# STM32.net
KiCad netlist of a schematic drawn in Altium Designer
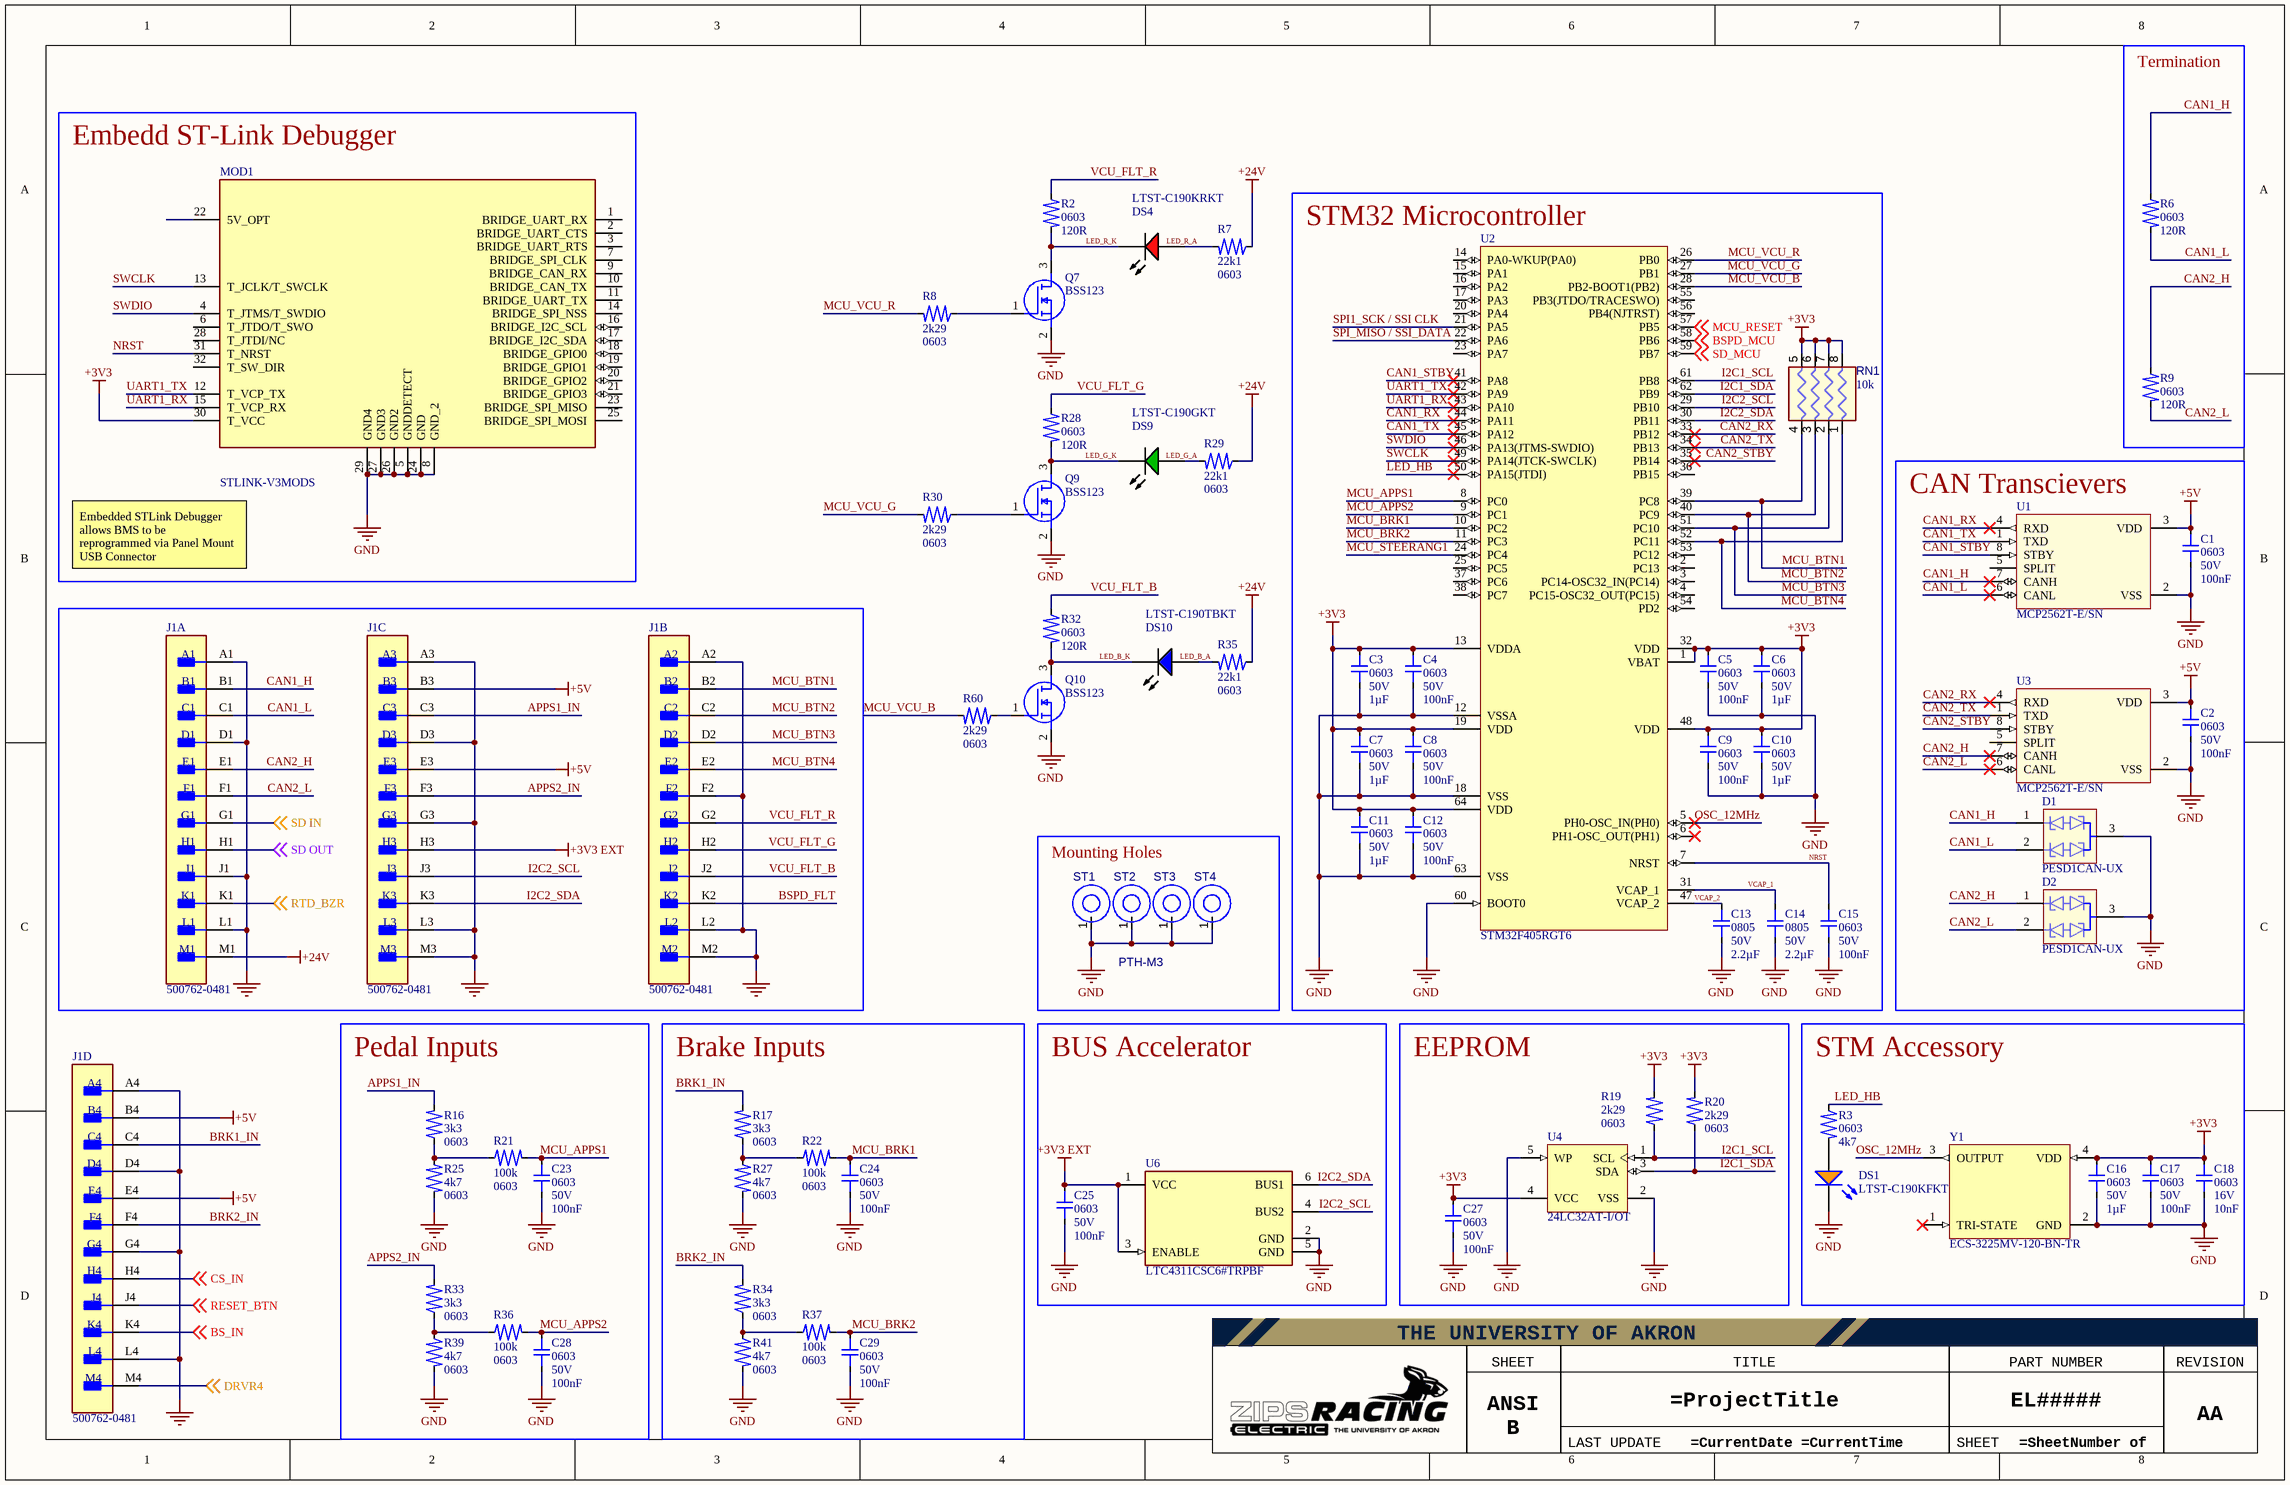
[diagram p0: STM32.SchDoc]

(export (version "E")
  (design (tool "Eeschema 10.0.6"))
  (components
    (comp (ref "C1")
      (value "100nF")
      (footprint "0603")
      (description "Capacitor, 0603, 5%")
      (fields (field (name "VOLTAGE") "50V") (field (name "Comment") "Capacitor 100nF 0603 5%"))
      (libsource (lib "Zips Racing Electric") (part "CAP-0603"))
    )
    (comp (ref "C2")
      (value "100nF")
      (footprint "0603")
      (description "Capacitor, 0603, 5%")
      (fields (field (name "VOLTAGE") "50V") (field (name "Comment") "Capacitor 100nF 0603 5%"))
      (libsource (lib "Zips Racing Electric") (part "CAP-0603"))
    )
    (comp (ref "C3")
      (value "1µF")
      (footprint "0603")
      (description "Capacitor, 0603, 5%")
      (fields (field (name "VOLTAGE") "50V") (field (name "Comment") "Capacitor 1uF 0603 5%"))
      (libsource (lib "Zips Racing Electric") (part "CAP-0603"))
    )
    (comp (ref "C4")
      (value "100nF")
      (footprint "0603")
      (description "Capacitor, 0603, 5%")
      (fields (field (name "VOLTAGE") "50V") (field (name "Comment") "Capacitor 100nF 0603 5%"))
      (libsource (lib "Zips Racing Electric") (part "CAP-0603"))
    )
    (comp (ref "C5")
      (value "100nF")
      (footprint "0603")
      (description "Capacitor, 0603, 5%")
      (fields (field (name "VOLTAGE") "50V") (field (name "Comment") "Capacitor 100nF 0603 5%"))
      (libsource (lib "Zips Racing Electric") (part "CAP-0603"))
    )
    (comp (ref "C6")
      (value "1µF")
      (footprint "0603")
      (description "Capacitor, 0603, 5%")
      (fields (field (name "VOLTAGE") "50V") (field (name "Comment") "Capacitor 1uF 0603 5%"))
      (libsource (lib "Zips Racing Electric") (part "CAP-0603"))
    )
    (comp (ref "C7")
      (value "1µF")
      (footprint "0603")
      (description "Capacitor, 0603, 5%")
      (fields (field (name "VOLTAGE") "50V") (field (name "Comment") "Capacitor 1uF 0603 5%"))
      (libsource (lib "Zips Racing Electric") (part "CAP-0603"))
    )
    (comp (ref "C8")
      (value "100nF")
      (footprint "0603")
      (description "Capacitor, 0603, 5%")
      (fields (field (name "VOLTAGE") "50V") (field (name "Comment") "Capacitor 100nF 0603 5%"))
      (libsource (lib "Zips Racing Electric") (part "CAP-0603"))
    )
    (comp (ref "C9")
      (value "100nF")
      (footprint "0603")
      (description "Capacitor, 0603, 5%")
      (fields (field (name "VOLTAGE") "50V") (field (name "Comment") "Capacitor 100nF 0603 5%"))
      (libsource (lib "Zips Racing Electric") (part "CAP-0603"))
    )
    (comp (ref "C10")
      (value "1µF")
      (footprint "0603")
      (description "Capacitor, 0603, 5%")
      (fields (field (name "VOLTAGE") "50V") (field (name "Comment") "Capacitor 1uF 0603 5%"))
      (libsource (lib "Zips Racing Electric") (part "CAP-0603"))
    )
    (comp (ref "C11")
      (value "1µF")
      (footprint "0603")
      (description "Capacitor, 0603, 5%")
      (fields (field (name "VOLTAGE") "50V") (field (name "Comment") "Capacitor 1uF 0603 5%"))
      (libsource (lib "Zips Racing Electric") (part "CAP-0603"))
    )
    (comp (ref "C12")
      (value "100nF")
      (footprint "0603")
      (description "Capacitor, 0603, 5%")
      (fields (field (name "VOLTAGE") "50V") (field (name "Comment") "Capacitor 100nF 0603 5%"))
      (libsource (lib "Zips Racing Electric") (part "CAP-0603"))
    )
    (comp (ref "C13")
      (value "2.2µF")
      (footprint "0805")
      (description "Capacitor, 0805, 5%")
      (fields (field (name "VOLTAGE") "50V") (field (name "Comment") "Capacitor 2.2F 0805 5%"))
      (libsource (lib "Zips Racing Electric") (part "CAP-0603"))
    )
    (comp (ref "C14")
      (value "2.2µF")
      (footprint "0805")
      (description "Capacitor, 0805, 5%")
      (fields (field (name "VOLTAGE") "50V") (field (name "Comment") "Capacitor 2.2F 0805 5%"))
      (libsource (lib "Zips Racing Electric") (part "CAP-0603"))
    )
    (comp (ref "C15")
      (value "100nF")
      (footprint "0603")
      (description "Capacitor, 0603, 5%")
      (fields (field (name "VOLTAGE") "50V") (field (name "Comment") "Capacitor 100nF 0603 5%"))
      (libsource (lib "Zips Racing Electric") (part "CAP-0603"))
    )
    (comp (ref "C16")
      (value "1µF")
      (footprint "0603")
      (description "Capacitor, 0603, 5%")
      (fields (field (name "VOLTAGE") "50V") (field (name "Comment") "Capacitor 1uF 0603 5%"))
      (libsource (lib "Zips Racing Electric") (part "CAP-0603"))
    )
    (comp (ref "C17")
      (value "100nF")
      (footprint "0603")
      (description "Capacitor, 0603, 5%")
      (fields (field (name "VOLTAGE") "50V") (field (name "Comment") "Capacitor 100nF 0603 5%"))
      (libsource (lib "Zips Racing Electric") (part "CAP-0603"))
    )
    (comp (ref "C18")
      (value "10nF")
      (footprint "0603")
      (description "Capacitor, 0603, 5%")
      (fields (field (name "VOLTAGE") "16V") (field (name "Comment") "Capacitor 10nF 0603 5%"))
      (libsource (lib "Zips Racing Electric") (part "CAP-0603"))
    )
    (comp (ref "C23")
      (value "100nF")
      (footprint "0603")
      (description "Capacitor, 0603, 5%")
      (fields (field (name "VOLTAGE") "50V") (field (name "Comment") "Capacitor 100nF 0603 5%"))
      (libsource (lib "Zips Racing Electric") (part "CAP-0603"))
    )
    (comp (ref "C24")
      (value "100nF")
      (footprint "0603")
      (description "Capacitor, 0603, 5%")
      (fields (field (name "VOLTAGE") "50V") (field (name "Comment") "Capacitor 100nF 0603 5%"))
      (libsource (lib "Zips Racing Electric") (part "CAP-0603"))
    )
    (comp (ref "C25")
      (value "100nF")
      (footprint "0603")
      (description "Capacitor, 0603, 5%")
      (fields (field (name "VOLTAGE") "50V") (field (name "Comment") "Capacitor 100nF 0603 5%"))
      (libsource (lib "Zips Racing Electric") (part "CAP-0603"))
    )
    (comp (ref "C27")
      (value "100nF")
      (footprint "0603")
      (description "Capacitor, 0603, 5%")
      (fields (field (name "VOLTAGE") "50V") (field (name "Comment") "Capacitor 100nF 0603 5%"))
      (libsource (lib "Zips Racing Electric") (part "CAP-0603"))
    )
    (comp (ref "C28")
      (value "100nF")
      (footprint "0603")
      (description "Capacitor, 0603, 5%")
      (fields (field (name "VOLTAGE") "50V") (field (name "Comment") "Capacitor 100nF 0603 5%"))
      (libsource (lib "Zips Racing Electric") (part "CAP-0603"))
    )
    (comp (ref "C29")
      (value "100nF")
      (footprint "0603")
      (description "Capacitor, 0603, 5%")
      (fields (field (name "VOLTAGE") "50V") (field (name "Comment") "Capacitor 100nF 0603 5%"))
      (libsource (lib "Zips Racing Electric") (part "CAP-0603"))
    )
    (comp (ref "D1")
      (value "PESD1CAN-UX")
      (footprint "FP-SOT323-MFG")
      (description "Trans Voltage Suppressor Diode, 150W, 24V V(RWM), Bidirectional, 2 Element, Silicon")
      (libsource (lib "Zips Racing Electric") (part "04d57993b6b7b0f5b3c95ba4f97dea0"))
    )
    (comp (ref "D2")
      (value "PESD1CAN-UX")
      (footprint "FP-SOT323-MFG")
      (description "Trans Voltage Suppressor Diode, 150W, 24V V(RWM), Bidirectional, 2 Element, Silicon")
      (libsource (lib "Zips Racing Electric") (part "04d57993b6b7b0f5b3c95ba4f97dea0"))
    )
    (comp (ref "DS1")
      (value "LTST-C190KFKT")
      (footprint "LTST-C190KFKT_V")
      (description "LED Uni-Color Orange, 75 mW, 30 mA, -35 to 85 degC, 2-Pin SMD, RoHS, Tape and Reel")
      (fields (field (name "POWER") "75mW") (field (name "MANUFACTURER") "Lite-On"))
      (libsource (lib "Zips Racing Electric") (part "LED-ORANGE-AK-2"))
    )
    (comp (ref "DS4")
      (value "LTST-C190KRKT")
      (footprint "LTST-C191KRKT_V")
      (description "LED Uni-Color Red, 62.5 mW, 25 mA, -30 to 85 degC, 2-Pin SMD, RoHS, Tape and Reel")
      (fields (field (name "POWER") "75mW") (field (name "MANUFACTURER") "Lite-On"))
      (libsource (lib "Zips Racing Electric") (part "LED-RED-AK-2"))
    )
    (comp (ref "DS9")
      (value "LTST-C190GKT")
      (footprint "LTST-C190GKT_V")
      (description "LED Uni-Color Green, 100 mW, 30 mA, -55 to 85 degC, 2-Pin SMD, RoHS, Tape and Reel")
      (fields (field (name "POWER") "100mW") (field (name "MANUFACTURER") "Lite-On"))
      (libsource (lib "Zips Racing Electric") (part "LED-GREEN-AK-2"))
    )
    (comp (ref "DS10")
      (value "LTST-C190TBKT")
      (footprint "LTST-C190TBKT-2_V")
      (description "LED Uni-Color Blue, 76 mW, 20 mA, -20 to 80 degC, 2-Pin SMD, RoHS, Tape and Reel")
      (fields (field (name "MANUFACTURER") "Lite-On"))
      (libsource (lib "Zips Racing Electric") (part "LED-BLUE-AK-2"))
    )
    (comp (ref "J1")
      (value "500762-0481")
      (footprint "FP-500762-0481-MFG")
      (libsource (lib "Zips Racing Electric") (part "63bd5f320afc6d0a360c9db9c10dcc9"))
    )
    (comp (ref "MOD1")
      (value "STLINK-V3MODS")
      (footprint "STLINK-V3MODS-Footprint-1")
      (description "STLINK V3 Debugger Board Module")
      (libsource (lib "Zips Racing Electric") (part "STLINK-V3MODS-Symbol-1"))
    )
    (comp (ref "Q7")
      (value "BSS123")
      (footprint "SOT96P237X111-3N")
      (description "MOSFET N-CH 100V 170MA SOT23-3")
      (fields
        (field (name "MOUSER PART NUMBER") "512-BSS123")
        (field (name "SOURCE") "Zips_Racing_Electric.SchLib")
      )
      (libsource (lib "Zips Racing Electric") (part "BSS123"))
    )
    (comp (ref "Q9")
      (value "BSS123")
      (footprint "SOT96P237X111-3N")
      (description "MOSFET N-CH 100V 170MA SOT23-3")
      (fields
        (field (name "MOUSER PART NUMBER") "512-BSS123")
        (field (name "SOURCE") "Zips_Racing_Electric.SchLib")
      )
      (libsource (lib "Zips Racing Electric") (part "BSS123"))
    )
    (comp (ref "Q10")
      (value "BSS123")
      (footprint "SOT96P237X111-3N")
      (description "MOSFET N-CH 100V 170MA SOT23-3")
      (fields
        (field (name "MOUSER PART NUMBER") "512-BSS123")
        (field (name "SOURCE") "Zips_Racing_Electric.SchLib")
      )
      (libsource (lib "Zips Racing Electric") (part "BSS123"))
    )
    (comp (ref "R2")
      (value "120R")
      (footprint "0603")
      (description "Resistor, 0603, 1%, 1/10W")
      (fields (field (name "TOLERANCE") "1%") (field (name "POWER") "100mW"))
      (libsource (lib "Zips Racing Electric") (part "RES-0603"))
    )
    (comp (ref "R3")
      (value "4k7")
      (footprint "0603")
      (description "Resistor, 0603, 1%, 1/10W")
      (fields (field (name "TOLERANCE") "1%") (field (name "POWER") "100mW"))
      (libsource (lib "Zips Racing Electric") (part "RES-0603"))
    )
    (comp (ref "R6")
      (value "120R")
      (footprint "0603")
      (description "Resistor, 0603, 1%, 1/10W")
      (fields (field (name "TOLERANCE") "1%") (field (name "POWER") "100mW"))
      (libsource (lib "Zips Racing Electric") (part "RES-0603"))
    )
    (comp (ref "R7")
      (value "22k1")
      (footprint "0603")
      (description "Resistor, 0603, 1%, 1/10W")
      (fields (field (name "TOLERANCE") "1%") (field (name "POWER") "100mW"))
      (libsource (lib "Zips Racing Electric") (part "RES-0603"))
    )
    (comp (ref "R8")
      (value "2k29")
      (footprint "0603")
      (description "Resistor, 0603, 1%, 1/10W")
      (fields (field (name "TOLERANCE") "1%") (field (name "POWER") "100mW"))
      (libsource (lib "Zips Racing Electric") (part "RES-0603"))
    )
    (comp (ref "R9")
      (value "120R")
      (footprint "0603")
      (description "Resistor, 0603, 1%, 1/10W")
      (fields (field (name "TOLERANCE") "1%") (field (name "POWER") "100mW"))
      (libsource (lib "Zips Racing Electric") (part "RES-0603"))
    )
    (comp (ref "R16")
      (value "3k3")
      (footprint "0603")
      (description "Resistor, 0603, 1%, 1/10W")
      (fields (field (name "TOLERANCE") "1%") (field (name "POWER") "100mW"))
      (libsource (lib "Zips Racing Electric") (part "RES-0603"))
    )
    (comp (ref "R17")
      (value "3k3")
      (footprint "0603")
      (description "Resistor, 0603, 1%, 1/10W")
      (fields (field (name "TOLERANCE") "1%") (field (name "POWER") "100mW"))
      (libsource (lib "Zips Racing Electric") (part "RES-0603"))
    )
    (comp (ref "R19")
      (value "2k29")
      (footprint "0603")
      (description "Resistor, 0603, 1%, 1/10W")
      (fields (field (name "TOLERANCE") "1%") (field (name "POWER") "100mW"))
      (libsource (lib "Zips Racing Electric") (part "RES-0603"))
    )
    (comp (ref "R20")
      (value "2k29")
      (footprint "0603")
      (description "Resistor, 0603, 1%, 1/10W")
      (fields (field (name "TOLERANCE") "1%") (field (name "POWER") "100mW"))
      (libsource (lib "Zips Racing Electric") (part "RES-0603"))
    )
    (comp (ref "R21")
      (value "100k")
      (footprint "0603")
      (description "Resistor, 0603, 1%, 1/10W")
      (fields (field (name "POWER") "100mW") (field (name "TOLERANCE") "1%"))
      (libsource (lib "Zips Racing Electric") (part "RES-0603"))
    )
    (comp (ref "R22")
      (value "100k")
      (footprint "0603")
      (description "Resistor, 0603, 1%, 1/10W")
      (fields (field (name "POWER") "100mW") (field (name "TOLERANCE") "1%"))
      (libsource (lib "Zips Racing Electric") (part "RES-0603"))
    )
    (comp (ref "R25")
      (value "4k7")
      (footprint "0603")
      (description "Resistor, 0603, 1%, 1/10W")
      (fields (field (name "TOLERANCE") "1%") (field (name "POWER") "100mW"))
      (libsource (lib "Zips Racing Electric") (part "RES-0603"))
    )
    (comp (ref "R27")
      (value "4k7")
      (footprint "0603")
      (description "Resistor, 0603, 1%, 1/10W")
      (fields (field (name "TOLERANCE") "1%") (field (name "POWER") "100mW"))
      (libsource (lib "Zips Racing Electric") (part "RES-0603"))
    )
    (comp (ref "R28")
      (value "120R")
      (footprint "0603")
      (description "Resistor, 0603, 1%, 1/10W")
      (fields (field (name "TOLERANCE") "1%") (field (name "POWER") "100mW"))
      (libsource (lib "Zips Racing Electric") (part "RES-0603"))
    )
    (comp (ref "R29")
      (value "22k1")
      (footprint "0603")
      (description "Resistor, 0603, 1%, 1/10W")
      (fields (field (name "TOLERANCE") "1%") (field (name "POWER") "100mW"))
      (libsource (lib "Zips Racing Electric") (part "RES-0603"))
    )
    (comp (ref "R30")
      (value "2k29")
      (footprint "0603")
      (description "Resistor, 0603, 1%, 1/10W")
      (fields (field (name "TOLERANCE") "1%") (field (name "POWER") "100mW"))
      (libsource (lib "Zips Racing Electric") (part "RES-0603"))
    )
    (comp (ref "R32")
      (value "120R")
      (footprint "0603")
      (description "Resistor, 0603, 1%, 1/10W")
      (fields (field (name "TOLERANCE") "1%") (field (name "POWER") "100mW"))
      (libsource (lib "Zips Racing Electric") (part "RES-0603"))
    )
    (comp (ref "R33")
      (value "3k3")
      (footprint "0603")
      (description "Resistor, 0603, 1%, 1/10W")
      (fields (field (name "TOLERANCE") "1%") (field (name "POWER") "100mW"))
      (libsource (lib "Zips Racing Electric") (part "RES-0603"))
    )
    (comp (ref "R34")
      (value "3k3")
      (footprint "0603")
      (description "Resistor, 0603, 1%, 1/10W")
      (fields (field (name "TOLERANCE") "1%") (field (name "POWER") "100mW"))
      (libsource (lib "Zips Racing Electric") (part "RES-0603"))
    )
    (comp (ref "R35")
      (value "22k1")
      (footprint "0603")
      (description "Resistor, 0603, 1%, 1/10W")
      (fields (field (name "TOLERANCE") "1%") (field (name "POWER") "100mW"))
      (libsource (lib "Zips Racing Electric") (part "RES-0603"))
    )
    (comp (ref "R36")
      (value "100k")
      (footprint "0603")
      (description "Resistor, 0603, 1%, 1/10W")
      (fields (field (name "POWER") "100mW") (field (name "TOLERANCE") "1%"))
      (libsource (lib "Zips Racing Electric") (part "RES-0603"))
    )
    (comp (ref "R37")
      (value "100k")
      (footprint "0603")
      (description "Resistor, 0603, 1%, 1/10W")
      (fields (field (name "POWER") "100mW") (field (name "TOLERANCE") "1%"))
      (libsource (lib "Zips Racing Electric") (part "RES-0603"))
    )
    (comp (ref "R39")
      (value "4k7")
      (footprint "0603")
      (description "Resistor, 0603, 1%, 1/10W")
      (fields (field (name "TOLERANCE") "1%") (field (name "POWER") "100mW"))
      (libsource (lib "Zips Racing Electric") (part "RES-0603"))
    )
    (comp (ref "R41")
      (value "4k7")
      (footprint "0603")
      (description "Resistor, 0603, 1%, 1/10W")
      (fields (field (name "TOLERANCE") "1%") (field (name "POWER") "100mW"))
      (libsource (lib "Zips Racing Electric") (part "RES-0603"))
    )
    (comp (ref "R60")
      (value "2k29")
      (footprint "0603")
      (description "Resistor, 0603, 1%, 1/10W")
      (fields (field (name "TOLERANCE") "1%") (field (name "POWER") "100mW"))
      (libsource (lib "Zips Racing Electric") (part "RES-0603"))
    )
    (comp (ref "RN1")
      (value "10k")
      (footprint "BOUR-CAY16-J4_V")
      (description "Chip Resistor Array, 10 KOhm, +/- 5%, 62.5 mW, -55 to 125 degC, 8-Pin SMD, RoHS, Tape and Reel")
      (fields (field (name "MANUFACTURER") "Bourns") (field (name "TOLERANCE") "5%"))
      (libsource (lib "Zips Racing Electric") (part "RES-P-4"))
    )
    (comp (ref "ST1")
      (value "PTH-M3")
      (footprint "PTH-M2D5X5")
      (description "M3 Plated Thru-Hole  (3.2mm), 7mm pad, 10 mm keep out zone")
      (libsource (lib "Zips Racing Electric") (part "CMP-00028-00000-1"))
    )
    (comp (ref "ST2")
      (value "PTH-M3")
      (footprint "PTH-M2D5X5")
      (description "M3 Plated Thru-Hole  (3.2mm), 7mm pad, 10 mm keep out zone")
      (libsource (lib "Zips Racing Electric") (part "CMP-00028-00000-1"))
    )
    (comp (ref "ST3")
      (value "PTH-M3")
      (footprint "PTH-M2D5X5")
      (description "M3 Plated Thru-Hole  (3.2mm), 7mm pad, 10 mm keep out zone")
      (libsource (lib "Zips Racing Electric") (part "CMP-00028-00000-1"))
    )
    (comp (ref "ST4")
      (value "PTH-M3")
      (footprint "PTH-M2D5X5")
      (description "M3 Plated Thru-Hole  (3.2mm), 7mm pad, 10 mm keep out zone")
      (libsource (lib "Zips Racing Electric") (part "CMP-00028-00000-1"))
    )
    (comp (ref "U1")
      (value "MCP2562T-E/SN")
      (footprint "MCP2562T-E_SN-Footprint-1")
      (description "IC TXRX CAN 8SOIC")
      (libsource (lib "Zips Racing Electric") (part "MCP2562T-E_SN-Symbol-1"))
    )
    (comp (ref "U2")
      (value "STM32F405RGT6")
      (footprint "STM-LQFP64_V")
      (description "RISC Microcontroller, 32-Bit, FLASH, CORTEX-M4 CPU, 168MHz, CMOS, PQFP64")
      (libsource (lib "Zips Racing Electric") (part "MC-ARM-STM32F4X5-SQ64"))
    )
    (comp (ref "U3")
      (value "MCP2562T-E/SN")
      (footprint "MCP2562T-E_SN-Footprint-1")
      (description "IC TXRX CAN 8SOIC")
      (libsource (lib "Zips Racing Electric") (part "MCP2562T-E_SN-Symbol-1"))
    )
    (comp (ref "U4")
      (value "24LC32AT-I/OT")
      (footprint "SOT-23-OT5_L")
      (description "EEPROM, 4KX8, Serial, CMOS, PDSO5")
      (libsource (lib "Zips Racing Electric") (part "MEM-SEEPROM-24AA16-OT-5"))
    )
    (comp (ref "U6")
      (value "LTC4311CSC6#TRPBF")
      (footprint "FP-SC6-6-05-08-1638-IPC_A")
      (description "Analog Circuit, 1 Func, PDSO6")
      (libsource (lib "Zips Racing Electric") (part "249912f688ef07af999f1014998f853"))
    )
    (comp (ref "Y1")
      (value "ECS-3225MV-120-BN-TR")
      (footprint "ECS-3225MV-120-BN-TR-Footprint-1")
      (description "HCMOS Output Clock Oscillator, 12MHz Nom")
      (libsource (lib "Zips Racing Electric") (part "ECS-3225MV-120-BN-TR-Symbol-1"))
    )
  )
  (nets
    (net (code "1") (name "+3V3") (class "Default")
      (node (ref "C10") (pin "2") (pinfunction "2_2") (pintype "passive"))
      (node (ref "C11") (pin "2") (pinfunction "2_2") (pintype "passive"))
      (node (ref "C12") (pin "2") (pinfunction "2_2") (pintype "passive"))
      (node (ref "C16") (pin "2") (pinfunction "2_2") (pintype "passive"))
      (node (ref "C17") (pin "2") (pinfunction "2_2") (pintype "passive"))
      (node (ref "C18") (pin "2") (pinfunction "2_2") (pintype "passive"))
      (node (ref "C27") (pin "2") (pinfunction "2_2") (pintype "passive"))
      (node (ref "C3") (pin "2") (pinfunction "2_2") (pintype "passive"))
      (node (ref "C4") (pin "2") (pinfunction "2_2") (pintype "passive"))
      (node (ref "C5") (pin "2") (pinfunction "2_2") (pintype "passive"))
      (node (ref "C6") (pin "2") (pinfunction "2_2") (pintype "passive"))
      (node (ref "C7") (pin "2") (pinfunction "2_2") (pintype "passive"))
      (node (ref "C8") (pin "2") (pinfunction "2_2") (pintype "passive"))
      (node (ref "C9") (pin "2") (pinfunction "2_2") (pintype "passive"))
      (node (ref "MOD1") (pin "30") (pinfunction "T_VCC_30") (pintype "passive"))
      (node (ref "R19") (pin "2") (pinfunction "2_2") (pintype "passive"))
      (node (ref "R20") (pin "2") (pinfunction "2_2") (pintype "passive"))
      (node (ref "RN1") (pin "5") (pinfunction "2_5") (pintype "passive"))
      (node (ref "RN1") (pin "6") (pinfunction "2_6") (pintype "passive"))
      (node (ref "RN1") (pin "7") (pinfunction "2_7") (pintype "passive"))
      (node (ref "RN1") (pin "8") (pinfunction "2_8") (pintype "passive"))
      (node (ref "U2") (pin "1") (pinfunction "VBAT_1") (pintype "power_in"))
      (node (ref "U2") (pin "13") (pinfunction "VDDA_13") (pintype "power_in"))
      (node (ref "U2") (pin "19") (pinfunction "VDD_19") (pintype "power_in"))
      (node (ref "U2") (pin "32") (pinfunction "VDD_32") (pintype "power_in"))
      (node (ref "U2") (pin "48") (pinfunction "VDD_48") (pintype "power_in"))
      (node (ref "U2") (pin "64") (pinfunction "VDD_64") (pintype "power_in"))
      (node (ref "U4") (pin "4") (pinfunction "VCC_4") (pintype "power_in"))
      (node (ref "Y1") (pin "4") (pinfunction "VDD_4") (pintype "input"))
    )
    (net (code "2") (name "+3V3 EXT") (class "Default")
      (node (ref "C25") (pin "2") (pinfunction "2_2") (pintype "passive"))
      (node (ref "J1") (pin "H3") (pinfunction "H3_H3") (pintype "passive"))
      (node (ref "U6") (pin "1") (pinfunction "VCC_1") (pintype "power_in"))
      (node (ref "U6") (pin "3") (pinfunction "ENABLE_3") (pintype "input"))
    )
    (net (code "3") (name "+5V") (class "Default")
      (node (ref "C1") (pin "2") (pinfunction "2_2") (pintype "passive"))
      (node (ref "C2") (pin "2") (pinfunction "2_2") (pintype "passive"))
      (node (ref "J1") (pin "B3") (pinfunction "B3_B3") (pintype "passive"))
      (node (ref "J1") (pin "B4") (pinfunction "B4_B4") (pintype "passive"))
      (node (ref "J1") (pin "E3") (pinfunction "E3_E3") (pintype "passive"))
      (node (ref "J1") (pin "E4") (pinfunction "E4_E4") (pintype "passive"))
      (node (ref "U1") (pin "3") (pinfunction "VDD_3") (pintype "power_in"))
      (node (ref "U3") (pin "3") (pinfunction "VDD_3") (pintype "power_in"))
    )
    (net (code "4") (name "+24V") (class "Default")
      (node (ref "J1") (pin "M1") (pinfunction "M1_M1") (pintype "passive"))
      (node (ref "R29") (pin "1") (pinfunction "1_1") (pintype "passive"))
      (node (ref "R35") (pin "1") (pinfunction "1_1") (pintype "passive"))
      (node (ref "R7") (pin "1") (pinfunction "1_1") (pintype "passive"))
    )
    (net (code "5") (name "/APPS1_IN") (class "Default")
      (node (ref "J1") (pin "C3") (pinfunction "C3_C3") (pintype "passive"))
      (node (ref "R16") (pin "2") (pinfunction "2_2") (pintype "passive"))
    )
    (net (code "6") (name "/APPS2_IN") (class "Default")
      (node (ref "J1") (pin "F3") (pinfunction "F3_F3") (pintype "passive"))
      (node (ref "R33") (pin "2") (pinfunction "2_2") (pintype "passive"))
    )
    (net (code "7") (name "/BRK1_IN") (class "Default")
      (node (ref "J1") (pin "C4") (pinfunction "C4_C4") (pintype "passive"))
      (node (ref "R17") (pin "2") (pinfunction "2_2") (pintype "passive"))
    )
    (net (code "8") (name "/BRK2_IN") (class "Default")
      (node (ref "J1") (pin "F4") (pinfunction "F4_F4") (pintype "passive"))
      (node (ref "R34") (pin "2") (pinfunction "2_2") (pintype "passive"))
    )
    (net (code "9") (name "/BSPD_FLT") (class "Default")
      (node (ref "J1") (pin "K2") (pinfunction "K2_K2") (pintype "passive"))
    )
    (net (code "10") (name "/CAN1_H") (class "Default")
      (node (ref "D1") (pin "1") (pinfunction "cathode_1_1") (pintype "passive"))
      (node (ref "J1") (pin "B1") (pinfunction "B1_B1") (pintype "passive"))
      (node (ref "R6") (pin "1") (pinfunction "1_1") (pintype "passive"))
      (node (ref "U1") (pin "7") (pinfunction "CANH_7") (pintype "bidirectional"))
    )
    (net (code "11") (name "/CAN1_L") (class "Default")
      (node (ref "D1") (pin "2") (pinfunction "cathode_2_2") (pintype "passive"))
      (node (ref "J1") (pin "C1") (pinfunction "C1_C1") (pintype "passive"))
      (node (ref "R6") (pin "2") (pinfunction "2_2") (pintype "passive"))
      (node (ref "U1") (pin "6") (pinfunction "CANL_6") (pintype "bidirectional"))
    )
    (net (code "12") (name "/CAN1_RX") (class "Default")
      (node (ref "U1") (pin "4") (pinfunction "RXD_4") (pintype "output"))
      (node (ref "U2") (pin "44") (pinfunction "PA11_44") (pintype "bidirectional"))
    )
    (net (code "13") (name "/CAN1_STBY") (class "Default")
      (node (ref "U1") (pin "8") (pinfunction "STBY_8") (pintype "input"))
      (node (ref "U2") (pin "41") (pinfunction "PA8_41") (pintype "bidirectional"))
    )
    (net (code "14") (name "/CAN1_TX") (class "Default")
      (node (ref "U1") (pin "1") (pinfunction "TXD_1") (pintype "input"))
      (node (ref "U2") (pin "45") (pinfunction "PA12_45") (pintype "bidirectional"))
    )
    (net (code "15") (name "/CAN2_H") (class "Default")
      (node (ref "D2") (pin "1") (pinfunction "cathode_1_1") (pintype "passive"))
      (node (ref "J1") (pin "E1") (pinfunction "E1_E1") (pintype "passive"))
      (node (ref "R9") (pin "1") (pinfunction "1_1") (pintype "passive"))
      (node (ref "U3") (pin "7") (pinfunction "CANH_7") (pintype "bidirectional"))
    )
    (net (code "16") (name "/CAN2_L") (class "Default")
      (node (ref "D2") (pin "2") (pinfunction "cathode_2_2") (pintype "passive"))
      (node (ref "J1") (pin "F1") (pinfunction "F1_F1") (pintype "passive"))
      (node (ref "R9") (pin "2") (pinfunction "2_2") (pintype "passive"))
      (node (ref "U3") (pin "6") (pinfunction "CANL_6") (pintype "bidirectional"))
    )
    (net (code "17") (name "/CAN2_RX") (class "Default")
      (node (ref "U2") (pin "33") (pinfunction "PB12_33") (pintype "bidirectional"))
      (node (ref "U3") (pin "4") (pinfunction "RXD_4") (pintype "output"))
    )
    (net (code "18") (name "/CAN2_STBY") (class "Default")
      (node (ref "U2") (pin "35") (pinfunction "PB14_35") (pintype "bidirectional"))
      (node (ref "U3") (pin "8") (pinfunction "STBY_8") (pintype "input"))
    )
    (net (code "19") (name "/CAN2_TX") (class "Default")
      (node (ref "U2") (pin "34") (pinfunction "PB13_34") (pintype "bidirectional"))
      (node (ref "U3") (pin "1") (pinfunction "TXD_1") (pintype "input"))
    )
    (net (code "20") (name "/I2C1_SCL") (class "Default")
      (node (ref "R19") (pin "1") (pinfunction "1_1") (pintype "passive"))
      (node (ref "U2") (pin "61") (pinfunction "PB8_61") (pintype "bidirectional"))
      (node (ref "U4") (pin "1") (pinfunction "SCL_1") (pintype "input"))
    )
    (net (code "21") (name "/I2C1_SDA") (class "Default")
      (node (ref "R20") (pin "1") (pinfunction "1_1") (pintype "passive"))
      (node (ref "U2") (pin "62") (pinfunction "PB9_62") (pintype "bidirectional"))
      (node (ref "U4") (pin "3") (pinfunction "SDA_3") (pintype "bidirectional"))
    )
    (net (code "22") (name "/I2C2_SCL") (class "Default")
      (node (ref "J1") (pin "J3") (pinfunction "J3_J3") (pintype "passive"))
      (node (ref "U2") (pin "29") (pinfunction "PB10_29") (pintype "bidirectional"))
      (node (ref "U6") (pin "4") (pinfunction "BUS2_4") (pintype "passive"))
    )
    (net (code "23") (name "/I2C2_SDA") (class "Default")
      (node (ref "J1") (pin "K3") (pinfunction "K3_K3") (pintype "passive"))
      (node (ref "U2") (pin "30") (pinfunction "PB11_30") (pintype "bidirectional"))
      (node (ref "U6") (pin "6") (pinfunction "BUS1_6") (pintype "passive"))
    )
    (net (code "24") (name "/LED_B_A") (class "Default")
      (node (ref "DS10") (pin "1") (pinfunction "A_1") (pintype "passive"))
      (node (ref "R35") (pin "2") (pinfunction "2_2") (pintype "passive"))
    )
    (net (code "25") (name "/LED_B_K") (class "Default")
      (node (ref "DS10") (pin "2") (pinfunction "K_2") (pintype "passive"))
      (node (ref "Q10") (pin "3") (pinfunction "D_3") (pintype "passive"))
      (node (ref "R32") (pin "2") (pinfunction "2_2") (pintype "passive"))
    )
    (net (code "26") (name "/LED_G_A") (class "Default")
      (node (ref "DS9") (pin "1") (pinfunction "A_1") (pintype "passive"))
      (node (ref "R29") (pin "2") (pinfunction "2_2") (pintype "passive"))
    )
    (net (code "27") (name "/LED_G_K") (class "Default")
      (node (ref "DS9") (pin "2") (pinfunction "K_2") (pintype "passive"))
      (node (ref "Q9") (pin "3") (pinfunction "D_3") (pintype "passive"))
      (node (ref "R28") (pin "2") (pinfunction "2_2") (pintype "passive"))
    )
    (net (code "28") (name "/LED_HB") (class "Default")
      (node (ref "R3") (pin "1") (pinfunction "1_1") (pintype "passive"))
      (node (ref "U2") (pin "50") (pinfunction "PA15(JTDI)_50") (pintype "bidirectional"))
    )
    (net (code "29") (name "/LED_R_A") (class "Default")
      (node (ref "DS4") (pin "1") (pinfunction "A_1") (pintype "passive"))
      (node (ref "R7") (pin "2") (pinfunction "2_2") (pintype "passive"))
    )
    (net (code "30") (name "/LED_R_K") (class "Default")
      (node (ref "DS4") (pin "2") (pinfunction "K_2") (pintype "passive"))
      (node (ref "Q7") (pin "3") (pinfunction "D_3") (pintype "passive"))
      (node (ref "R2") (pin "2") (pinfunction "2_2") (pintype "passive"))
    )
    (net (code "31") (name "/MCU_APPS1") (class "Default")
      (node (ref "C23") (pin "2") (pinfunction "2_2") (pintype "passive"))
      (node (ref "R21") (pin "2") (pinfunction "2_2") (pintype "passive"))
      (node (ref "U2") (pin "8") (pinfunction "PC0_8") (pintype "bidirectional"))
    )
    (net (code "32") (name "/MCU_APPS2") (class "Default")
      (node (ref "C28") (pin "2") (pinfunction "2_2") (pintype "passive"))
      (node (ref "R36") (pin "2") (pinfunction "2_2") (pintype "passive"))
      (node (ref "U2") (pin "9") (pinfunction "PC1_9") (pintype "bidirectional"))
    )
    (net (code "33") (name "/MCU_BRK1") (class "Default")
      (node (ref "C24") (pin "2") (pinfunction "2_2") (pintype "passive"))
      (node (ref "R22") (pin "2") (pinfunction "2_2") (pintype "passive"))
      (node (ref "U2") (pin "10") (pinfunction "PC2_10") (pintype "bidirectional"))
    )
    (net (code "34") (name "/MCU_BRK2") (class "Default")
      (node (ref "C29") (pin "2") (pinfunction "2_2") (pintype "passive"))
      (node (ref "R37") (pin "2") (pinfunction "2_2") (pintype "passive"))
      (node (ref "U2") (pin "11") (pinfunction "PC3_11") (pintype "bidirectional"))
    )
    (net (code "35") (name "/MCU_BTN1") (class "Default")
      (node (ref "J1") (pin "B2") (pinfunction "B2_B2") (pintype "passive"))
      (node (ref "RN1") (pin "4") (pinfunction "1_4") (pintype "passive"))
      (node (ref "U2") (pin "39") (pinfunction "PC8_39") (pintype "bidirectional"))
    )
    (net (code "36") (name "/MCU_BTN2") (class "Default")
      (node (ref "J1") (pin "C2") (pinfunction "C2_C2") (pintype "passive"))
      (node (ref "RN1") (pin "3") (pinfunction "1_3") (pintype "passive"))
      (node (ref "U2") (pin "40") (pinfunction "PC9_40") (pintype "bidirectional"))
    )
    (net (code "37") (name "/MCU_BTN3") (class "Default")
      (node (ref "J1") (pin "D2") (pinfunction "D2_D2") (pintype "passive"))
      (node (ref "RN1") (pin "2") (pinfunction "1_2") (pintype "passive"))
      (node (ref "U2") (pin "51") (pinfunction "PC10_51") (pintype "bidirectional"))
    )
    (net (code "38") (name "/MCU_BTN4") (class "Default")
      (node (ref "J1") (pin "E2") (pinfunction "E2_E2") (pintype "passive"))
      (node (ref "RN1") (pin "1") (pinfunction "1_1") (pintype "passive"))
      (node (ref "U2") (pin "52") (pinfunction "PC11_52") (pintype "bidirectional"))
    )
    (net (code "39") (name "/MCU_STEERANG1") (class "Default")
      (node (ref "U2") (pin "24") (pinfunction "PC4_24") (pintype "bidirectional"))
    )
    (net (code "40") (name "/MCU_VCU_B") (class "Default")
      (node (ref "R60") (pin "2") (pinfunction "2_2") (pintype "passive"))
      (node (ref "U2") (pin "28") (pinfunction "PB2-BOOT1(PB2)_28") (pintype "bidirectional"))
    )
    (net (code "41") (name "/MCU_VCU_G") (class "Default")
      (node (ref "R30") (pin "2") (pinfunction "2_2") (pintype "passive"))
      (node (ref "U2") (pin "27") (pinfunction "PB1_27") (pintype "bidirectional"))
    )
    (net (code "42") (name "/MCU_VCU_R") (class "Default")
      (node (ref "R8") (pin "2") (pinfunction "2_2") (pintype "passive"))
      (node (ref "U2") (pin "26") (pinfunction "PB0_26") (pintype "bidirectional"))
    )
    (net (code "43") (name "/NRST") (class "Default")
      (node (ref "C15") (pin "2") (pinfunction "2_2") (pintype "passive"))
      (node (ref "MOD1") (pin "31") (pinfunction "T_NRST_31") (pintype "passive"))
      (node (ref "U2") (pin "7") (pinfunction "NRST_7") (pintype "bidirectional"))
    )
    (net (code "44") (name "/OSC_12MHz") (class "Default")
      (node (ref "U2") (pin "5") (pinfunction "PH0-OSC_IN(PH0)_5") (pintype "bidirectional"))
      (node (ref "Y1") (pin "3") (pinfunction "OUTPUT_3") (pintype "output"))
    )
    (net (code "45") (name "/SPI1_SCK {slash} SSI CLK") (class "Default")
      (node (ref "U2") (pin "21") (pinfunction "PA5_21") (pintype "bidirectional"))
    )
    (net (code "46") (name "/SPI_MISO {slash} SSI_DATA") (class "Default")
      (node (ref "U2") (pin "22") (pinfunction "PA6_22") (pintype "bidirectional"))
    )
    (net (code "47") (name "/SWCLK") (class "Default")
      (node (ref "MOD1") (pin "13") (pinfunction "T_JCLK/T_SWCLK_13") (pintype "passive"))
      (node (ref "U2") (pin "49") (pinfunction "PA14(JTCK-SWCLK)_49") (pintype "bidirectional"))
    )
    (net (code "48") (name "/SWDIO") (class "Default")
      (node (ref "MOD1") (pin "4") (pinfunction "T_JTMS/T_SWDIO_4") (pintype "passive"))
      (node (ref "U2") (pin "46") (pinfunction "PA13(JTMS-SWDIO)_46") (pintype "bidirectional"))
    )
    (net (code "49") (name "/UART1_RX") (class "Default")
      (node (ref "MOD1") (pin "15") (pinfunction "T_VCP_RX_15") (pintype "passive"))
      (node (ref "U2") (pin "43") (pinfunction "PA10_43") (pintype "bidirectional"))
    )
    (net (code "50") (name "/UART1_TX") (class "Default")
      (node (ref "MOD1") (pin "12") (pinfunction "T_VCP_TX_12") (pintype "passive"))
      (node (ref "U2") (pin "42") (pinfunction "PA9_42") (pintype "bidirectional"))
    )
    (net (code "51") (name "/VCAP_1") (class "Default")
      (node (ref "C14") (pin "2") (pinfunction "2_2") (pintype "passive"))
      (node (ref "U2") (pin "31") (pinfunction "VCAP_1_31") (pintype "power_in"))
    )
    (net (code "52") (name "/VCAP_2") (class "Default")
      (node (ref "C13") (pin "2") (pinfunction "2_2") (pintype "passive"))
      (node (ref "U2") (pin "47") (pinfunction "VCAP_2_47") (pintype "power_in"))
    )
    (net (code "53") (name "/VCU_FLT_B") (class "Default")
      (node (ref "J1") (pin "J2") (pinfunction "J2_J2") (pintype "passive"))
      (node (ref "R32") (pin "1") (pinfunction "1_1") (pintype "passive"))
    )
    (net (code "54") (name "/VCU_FLT_G") (class "Default")
      (node (ref "J1") (pin "H2") (pinfunction "H2_H2") (pintype "passive"))
      (node (ref "R28") (pin "1") (pinfunction "1_1") (pintype "passive"))
    )
    (net (code "55") (name "/VCU_FLT_R") (class "Default")
      (node (ref "J1") (pin "G2") (pinfunction "G2_G2") (pintype "passive"))
      (node (ref "R2") (pin "1") (pinfunction "1_1") (pintype "passive"))
    )
    (net (code "56") (name "BSPD_MCU") (class "Default")
      (node (ref "U2") (pin "58") (pinfunction "PB6_58") (pintype "bidirectional"))
    )
    (net (code "57") (name "BS_IN") (class "Default")
      (node (ref "J1") (pin "K4") (pinfunction "K4_K4") (pintype "passive"))
    )
    (net (code "58") (name "CS_IN") (class "Default")
      (node (ref "J1") (pin "H4") (pinfunction "H4_H4") (pintype "passive"))
    )
    (net (code "59") (name "DRVR4") (class "Default")
      (node (ref "J1") (pin "M4") (pinfunction "M4_M4") (pintype "passive"))
    )
    (net (code "60") (name "GND") (class "Default")
      (node (ref "C1") (pin "1") (pinfunction "1_1") (pintype "passive"))
      (node (ref "C10") (pin "1") (pinfunction "1_1") (pintype "passive"))
      (node (ref "C11") (pin "1") (pinfunction "1_1") (pintype "passive"))
      (node (ref "C12") (pin "1") (pinfunction "1_1") (pintype "passive"))
      (node (ref "C13") (pin "1") (pinfunction "1_1") (pintype "passive"))
      (node (ref "C14") (pin "1") (pinfunction "1_1") (pintype "passive"))
      (node (ref "C15") (pin "1") (pinfunction "1_1") (pintype "passive"))
      (node (ref "C16") (pin "1") (pinfunction "1_1") (pintype "passive"))
      (node (ref "C17") (pin "1") (pinfunction "1_1") (pintype "passive"))
      (node (ref "C18") (pin "1") (pinfunction "1_1") (pintype "passive"))
      (node (ref "C2") (pin "1") (pinfunction "1_1") (pintype "passive"))
      (node (ref "C23") (pin "1") (pinfunction "1_1") (pintype "passive"))
      (node (ref "C24") (pin "1") (pinfunction "1_1") (pintype "passive"))
      (node (ref "C25") (pin "1") (pinfunction "1_1") (pintype "passive"))
      (node (ref "C27") (pin "1") (pinfunction "1_1") (pintype "passive"))
      (node (ref "C28") (pin "1") (pinfunction "1_1") (pintype "passive"))
      (node (ref "C29") (pin "1") (pinfunction "1_1") (pintype "passive"))
      (node (ref "C3") (pin "1") (pinfunction "1_1") (pintype "passive"))
      (node (ref "C4") (pin "1") (pinfunction "1_1") (pintype "passive"))
      (node (ref "C5") (pin "1") (pinfunction "1_1") (pintype "passive"))
      (node (ref "C6") (pin "1") (pinfunction "1_1") (pintype "passive"))
      (node (ref "C7") (pin "1") (pinfunction "1_1") (pintype "passive"))
      (node (ref "C8") (pin "1") (pinfunction "1_1") (pintype "passive"))
      (node (ref "C9") (pin "1") (pinfunction "1_1") (pintype "passive"))
      (node (ref "D1") (pin "3") (pinfunction "common_cathode_3") (pintype "passive"))
      (node (ref "D2") (pin "3") (pinfunction "common_cathode_3") (pintype "passive"))
      (node (ref "DS1") (pin "2") (pinfunction "K_2") (pintype "passive"))
      (node (ref "J1") (pin "A1") (pinfunction "A1_A1") (pintype "passive"))
      (node (ref "J1") (pin "A2") (pinfunction "A2_A2") (pintype "passive"))
      (node (ref "J1") (pin "A3") (pinfunction "A3_A3") (pintype "passive"))
      (node (ref "J1") (pin "A4") (pinfunction "A4_A4") (pintype "passive"))
      (node (ref "J1") (pin "D1") (pinfunction "D1_D1") (pintype "passive"))
      (node (ref "J1") (pin "D3") (pinfunction "D3_D3") (pintype "passive"))
      (node (ref "J1") (pin "D4") (pinfunction "D4_D4") (pintype "passive"))
      (node (ref "J1") (pin "F2") (pinfunction "F2_F2") (pintype "passive"))
      (node (ref "J1") (pin "G3") (pinfunction "G3_G3") (pintype "passive"))
      (node (ref "J1") (pin "G4") (pinfunction "G4_G4") (pintype "passive"))
      (node (ref "J1") (pin "J1") (pinfunction "J1_J1") (pintype "passive"))
      (node (ref "J1") (pin "L1") (pinfunction "L1_L1") (pintype "passive"))
      (node (ref "J1") (pin "L2") (pinfunction "L2_L2") (pintype "passive"))
      (node (ref "J1") (pin "L3") (pinfunction "L3_L3") (pintype "passive"))
      (node (ref "J1") (pin "L4") (pinfunction "L4_L4") (pintype "passive"))
      (node (ref "J1") (pin "M2") (pinfunction "M2_M2") (pintype "passive"))
      (node (ref "J1") (pin "M3") (pinfunction "M3_M3") (pintype "passive"))
      (node (ref "MOD1") (pin "24") (pinfunction "GND_24") (pintype "power_in"))
      (node (ref "MOD1") (pin "26") (pinfunction "GND2_26") (pintype "power_in"))
      (node (ref "MOD1") (pin "27") (pinfunction "GND3_27") (pintype "power_in"))
      (node (ref "MOD1") (pin "29") (pinfunction "GND4_29") (pintype "power_in"))
      (node (ref "MOD1") (pin "5") (pinfunction "GNDDETECT_5") (pintype "power_in"))
      (node (ref "MOD1") (pin "8") (pinfunction "GND_2_8") (pintype "power_in"))
      (node (ref "Q10") (pin "2") (pinfunction "S_2") (pintype "passive"))
      (node (ref "Q7") (pin "2") (pinfunction "S_2") (pintype "passive"))
      (node (ref "Q9") (pin "2") (pinfunction "S_2") (pintype "passive"))
      (node (ref "R25") (pin "2") (pinfunction "2_2") (pintype "passive"))
      (node (ref "R27") (pin "2") (pinfunction "2_2") (pintype "passive"))
      (node (ref "R39") (pin "2") (pinfunction "2_2") (pintype "passive"))
      (node (ref "R41") (pin "2") (pinfunction "2_2") (pintype "passive"))
      (node (ref "ST1") (pin "1") (pinfunction "H1_1") (pintype "passive"))
      (node (ref "ST2") (pin "1") (pinfunction "H1_1") (pintype "passive"))
      (node (ref "ST3") (pin "1") (pinfunction "H1_1") (pintype "passive"))
      (node (ref "ST4") (pin "1") (pinfunction "H1_1") (pintype "passive"))
      (node (ref "U1") (pin "2") (pinfunction "VSS_2") (pintype "power_in"))
      (node (ref "U2") (pin "12") (pinfunction "VSSA_12") (pintype "power_in"))
      (node (ref "U2") (pin "18") (pinfunction "VSS_18") (pintype "power_in"))
      (node (ref "U2") (pin "60") (pinfunction "BOOT0_60") (pintype "input"))
      (node (ref "U2") (pin "63") (pinfunction "VSS_63") (pintype "power_in"))
      (node (ref "U3") (pin "2") (pinfunction "VSS_2") (pintype "power_in"))
      (node (ref "U4") (pin "2") (pinfunction "VSS_2") (pintype "power_in"))
      (node (ref "U4") (pin "5") (pinfunction "WP_5") (pintype "input"))
      (node (ref "U6") (pin "2") (pinfunction "GND_2") (pintype "power_in"))
      (node (ref "U6") (pin "5") (pinfunction "GND_5") (pintype "power_in"))
      (node (ref "Y1") (pin "2") (pinfunction "GND_2") (pintype "power_in"))
    )
    (net (code "61") (name "MCU_RESET") (class "Default")
      (node (ref "U2") (pin "57") (pinfunction "PB5_57") (pintype "bidirectional"))
    )
    (net (code "62") (name "Net-(DS1-A)") (class "Default")
      (node (ref "DS1") (pin "1") (pinfunction "A_1") (pintype "passive"))
      (node (ref "R3") (pin "2") (pinfunction "2_2") (pintype "passive"))
    )
    (net (code "63") (name "Net-(Q7-G)") (class "Default")
      (node (ref "Q7") (pin "1") (pinfunction "G_1") (pintype "passive"))
      (node (ref "R8") (pin "1") (pinfunction "1_1") (pintype "passive"))
    )
    (net (code "64") (name "Net-(Q9-G)") (class "Default")
      (node (ref "Q9") (pin "1") (pinfunction "G_1") (pintype "passive"))
      (node (ref "R30") (pin "1") (pinfunction "1_1") (pintype "passive"))
    )
    (net (code "65") (name "Net-(Q10-G)") (class "Default")
      (node (ref "Q10") (pin "1") (pinfunction "G_1") (pintype "passive"))
      (node (ref "R60") (pin "1") (pinfunction "1_1") (pintype "passive"))
    )
    (net (code "66") (name "Net-(R16-Pad1)") (class "Default")
      (node (ref "R16") (pin "1") (pinfunction "1_1") (pintype "passive"))
      (node (ref "R21") (pin "1") (pinfunction "1_1") (pintype "passive"))
      (node (ref "R25") (pin "1") (pinfunction "1_1") (pintype "passive"))
    )
    (net (code "67") (name "Net-(R17-Pad1)") (class "Default")
      (node (ref "R17") (pin "1") (pinfunction "1_1") (pintype "passive"))
      (node (ref "R22") (pin "1") (pinfunction "1_1") (pintype "passive"))
      (node (ref "R27") (pin "1") (pinfunction "1_1") (pintype "passive"))
    )
    (net (code "68") (name "Net-(R33-Pad1)") (class "Default")
      (node (ref "R33") (pin "1") (pinfunction "1_1") (pintype "passive"))
      (node (ref "R36") (pin "1") (pinfunction "1_1") (pintype "passive"))
      (node (ref "R39") (pin "1") (pinfunction "1_1") (pintype "passive"))
    )
    (net (code "69") (name "Net-(R34-Pad1)") (class "Default")
      (node (ref "R34") (pin "1") (pinfunction "1_1") (pintype "passive"))
      (node (ref "R37") (pin "1") (pinfunction "1_1") (pintype "passive"))
      (node (ref "R41") (pin "1") (pinfunction "1_1") (pintype "passive"))
    )
    (net (code "70") (name "RESET_BTN") (class "Default")
      (node (ref "J1") (pin "J4") (pinfunction "J4_J4") (pintype "passive"))
    )
    (net (code "71") (name "RTD_BZR") (class "Default")
      (node (ref "J1") (pin "K1") (pinfunction "K1_K1") (pintype "passive"))
    )
    (net (code "72") (name "SD IN") (class "Default")
      (node (ref "J1") (pin "G1") (pinfunction "G1_G1") (pintype "passive"))
    )
    (net (code "73") (name "SD OUT") (class "Default")
      (node (ref "J1") (pin "H1") (pinfunction "H1_H1") (pintype "passive"))
    )
    (net (code "74") (name "SD_MCU") (class "Default")
      (node (ref "U2") (pin "59") (pinfunction "PB7_59") (pintype "bidirectional"))
    )
    (net (code "75") (name "unconnected-(MOD1-5V_OPT-Pad22)") (class "Default")
      (node (ref "MOD1") (pin "22") (pinfunction "5V_OPT_22") (pintype "passive"))
    )
    (net (code "76") (name "unconnected-(MOD1-BRIDGE_CAN_RX-Pad9)") (class "Default")
      (node (ref "MOD1") (pin "9") (pinfunction "BRIDGE_CAN_RX_9") (pintype "passive"))
    )
    (net (code "77") (name "unconnected-(MOD1-BRIDGE_CAN_TX-Pad10)") (class "Default")
      (node (ref "MOD1") (pin "10") (pinfunction "BRIDGE_CAN_TX_10") (pintype "passive"))
    )
    (net (code "78") (name "unconnected-(MOD1-BRIDGE_GPIO0-Pad18)") (class "Default")
      (node (ref "MOD1") (pin "18") (pinfunction "BRIDGE_GPIO0_18") (pintype "bidirectional"))
    )
    (net (code "79") (name "unconnected-(MOD1-BRIDGE_GPIO1-Pad19)") (class "Default")
      (node (ref "MOD1") (pin "19") (pinfunction "BRIDGE_GPIO1_19") (pintype "bidirectional"))
    )
    (net (code "80") (name "unconnected-(MOD1-BRIDGE_GPIO2-Pad20)") (class "Default")
      (node (ref "MOD1") (pin "20") (pinfunction "BRIDGE_GPIO2_20") (pintype "bidirectional"))
    )
    (net (code "81") (name "unconnected-(MOD1-BRIDGE_GPIO3-Pad21)") (class "Default")
      (node (ref "MOD1") (pin "21") (pinfunction "BRIDGE_GPIO3_21") (pintype "bidirectional"))
    )
    (net (code "82") (name "unconnected-(MOD1-BRIDGE_I2C_SCL-Pad16)") (class "Default")
      (node (ref "MOD1") (pin "16") (pinfunction "BRIDGE_I2C_SCL_16") (pintype "bidirectional"))
    )
    (net (code "83") (name "unconnected-(MOD1-BRIDGE_I2C_SDA-Pad17)") (class "Default")
      (node (ref "MOD1") (pin "17") (pinfunction "BRIDGE_I2C_SDA_17") (pintype "bidirectional"))
    )
    (net (code "84") (name "unconnected-(MOD1-BRIDGE_SPI_CLK-Pad7)") (class "Default")
      (node (ref "MOD1") (pin "7") (pinfunction "BRIDGE_SPI_CLK_7") (pintype "passive"))
    )
    (net (code "85") (name "unconnected-(MOD1-BRIDGE_SPI_MISO-Pad23)") (class "Default")
      (node (ref "MOD1") (pin "23") (pinfunction "BRIDGE_SPI_MISO_23") (pintype "passive"))
    )
    (net (code "86") (name "unconnected-(MOD1-BRIDGE_SPI_MOSI-Pad25)") (class "Default")
      (node (ref "MOD1") (pin "25") (pinfunction "BRIDGE_SPI_MOSI_25") (pintype "passive"))
    )
    (net (code "87") (name "unconnected-(MOD1-BRIDGE_SPI_NSS-Pad14)") (class "Default")
      (node (ref "MOD1") (pin "14") (pinfunction "BRIDGE_SPI_NSS_14") (pintype "passive"))
    )
    (net (code "88") (name "unconnected-(MOD1-BRIDGE_UART_CTS-Pad2)") (class "Default")
      (node (ref "MOD1") (pin "2") (pinfunction "BRIDGE_UART_CTS_2") (pintype "passive"))
    )
    (net (code "89") (name "unconnected-(MOD1-BRIDGE_UART_RTS-Pad3)") (class "Default")
      (node (ref "MOD1") (pin "3") (pinfunction "BRIDGE_UART_RTS_3") (pintype "passive"))
    )
    (net (code "90") (name "unconnected-(MOD1-BRIDGE_UART_RX-Pad1)") (class "Default")
      (node (ref "MOD1") (pin "1") (pinfunction "BRIDGE_UART_RX_1") (pintype "passive"))
    )
    (net (code "91") (name "unconnected-(MOD1-BRIDGE_UART_TX-Pad11)") (class "Default")
      (node (ref "MOD1") (pin "11") (pinfunction "BRIDGE_UART_TX_11") (pintype "passive"))
    )
    (net (code "92") (name "unconnected-(MOD1-T_JTDI{slash}NC-Pad28)") (class "Default")
      (node (ref "MOD1") (pin "28") (pinfunction "T_JTDI/NC_28") (pintype "passive"))
    )
    (net (code "93") (name "unconnected-(MOD1-T_JTDO{slash}T_SWO-Pad6)") (class "Default")
      (node (ref "MOD1") (pin "6") (pinfunction "T_JTDO/T_SWO_6") (pintype "passive"))
    )
    (net (code "94") (name "unconnected-(MOD1-T_SW_DIR-Pad32)") (class "Default")
      (node (ref "MOD1") (pin "32") (pinfunction "T_SW_DIR_32") (pintype "passive"))
    )
    (net (code "95") (name "unconnected-(U1-SPLIT-Pad5)") (class "Default")
      (node (ref "U1") (pin "5") (pinfunction "SPLIT_5") (pintype "passive"))
    )
    (net (code "96") (name "unconnected-(U2-PA0-WKUP(PA0)-Pad14)") (class "Default")
      (node (ref "U2") (pin "14") (pinfunction "PA0-WKUP(PA0)_14") (pintype "bidirectional"))
    )
    (net (code "97") (name "unconnected-(U2-PA1-Pad15)") (class "Default")
      (node (ref "U2") (pin "15") (pinfunction "PA1_15") (pintype "bidirectional"))
    )
    (net (code "98") (name "unconnected-(U2-PA2-Pad16)") (class "Default")
      (node (ref "U2") (pin "16") (pinfunction "PA2_16") (pintype "bidirectional"))
    )
    (net (code "99") (name "unconnected-(U2-PA3-Pad17)") (class "Default")
      (node (ref "U2") (pin "17") (pinfunction "PA3_17") (pintype "bidirectional"))
    )
    (net (code "100") (name "unconnected-(U2-PA4-Pad20)") (class "Default")
      (node (ref "U2") (pin "20") (pinfunction "PA4_20") (pintype "bidirectional"))
    )
    (net (code "101") (name "unconnected-(U2-PA7-Pad23)") (class "Default")
      (node (ref "U2") (pin "23") (pinfunction "PA7_23") (pintype "bidirectional"))
    )
    (net (code "102") (name "unconnected-(U2-PB3(JTDO{slash}TRACESWO)-Pad55)") (class "Default")
      (node (ref "U2") (pin "55") (pinfunction "PB3(JTDO/TRACESWO)_55") (pintype "bidirectional"))
    )
    (net (code "103") (name "unconnected-(U2-PB4(NJTRST)-Pad56)") (class "Default")
      (node (ref "U2") (pin "56") (pinfunction "PB4(NJTRST)_56") (pintype "bidirectional"))
    )
    (net (code "104") (name "unconnected-(U2-PB15-Pad36)") (class "Default")
      (node (ref "U2") (pin "36") (pinfunction "PB15_36") (pintype "bidirectional"))
    )
    (net (code "105") (name "unconnected-(U2-PC5-Pad25)") (class "Default")
      (node (ref "U2") (pin "25") (pinfunction "PC5_25") (pintype "bidirectional"))
    )
    (net (code "106") (name "unconnected-(U2-PC6-Pad37)") (class "Default")
      (node (ref "U2") (pin "37") (pinfunction "PC6_37") (pintype "bidirectional"))
    )
    (net (code "107") (name "unconnected-(U2-PC7-Pad38)") (class "Default")
      (node (ref "U2") (pin "38") (pinfunction "PC7_38") (pintype "bidirectional"))
    )
    (net (code "108") (name "unconnected-(U2-PC12-Pad53)") (class "Default")
      (node (ref "U2") (pin "53") (pinfunction "PC12_53") (pintype "bidirectional"))
    )
    (net (code "109") (name "unconnected-(U2-PC13-Pad2)") (class "Default")
      (node (ref "U2") (pin "2") (pinfunction "PC13_2") (pintype "bidirectional"))
    )
    (net (code "110") (name "unconnected-(U2-PC14-OSC32_IN(PC14)-Pad3)") (class "Default")
      (node (ref "U2") (pin "3") (pinfunction "PC14-OSC32_IN(PC14)_3") (pintype "bidirectional"))
    )
    (net (code "111") (name "unconnected-(U2-PC15-OSC32_OUT(PC15)-Pad4)") (class "Default")
      (node (ref "U2") (pin "4") (pinfunction "PC15-OSC32_OUT(PC15)_4") (pintype "bidirectional"))
    )
    (net (code "112") (name "unconnected-(U2-PD2-Pad54)") (class "Default")
      (node (ref "U2") (pin "54") (pinfunction "PD2_54") (pintype "bidirectional"))
    )
    (net (code "113") (name "unconnected-(U2-PH1-OSC_OUT(PH1)-Pad6)") (class "Default")
      (node (ref "U2") (pin "6") (pinfunction "PH1-OSC_OUT(PH1)_6") (pintype "bidirectional+no_connect"))
    )
    (net (code "114") (name "unconnected-(U3-SPLIT-Pad5)") (class "Default")
      (node (ref "U3") (pin "5") (pinfunction "SPLIT_5") (pintype "passive"))
    )
    (net (code "115") (name "unconnected-(Y1-TRI-STATE-Pad1)") (class "Default")
      (node (ref "Y1") (pin "1") (pinfunction "TRI-STATE_1") (pintype "input+no_connect"))
    )
  )
)
